# NodeMCU.net
KiCad netlist of a schematic drawn in Altium Designer
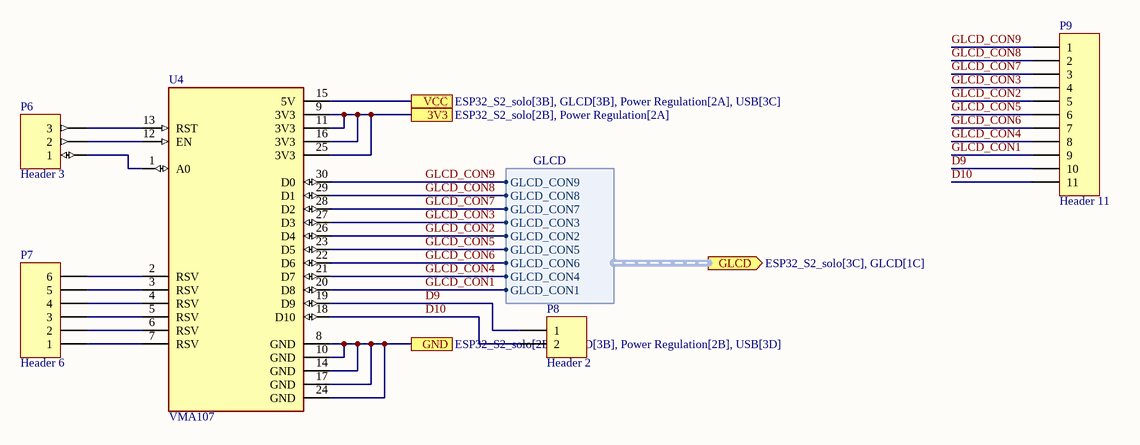
[diagram p0: NodeMCU.SchDoc]

(export (version "E")
  (design (tool "Eeschema 10.0.6"))
  (components
    (comp (ref "P6")
      (value "Header 3")
      (footprint "HDR1X3")
      (description "Header, 3-Pin")
      (fields (field (name "PUBLISHER") "Altium Limited"))
      (libsource (lib "Miscellaneous Connectors") (part "Header 3"))
    )
    (comp (ref "P7")
      (value "Header 6")
      (footprint "HDR1X6")
      (description "Header, 6-Pin")
      (fields (field (name "PUBLISHER") "Altium Limited"))
      (libsource (lib "Miscellaneous Connectors") (part "Header 6"))
    )
    (comp (ref "P8")
      (value "Header 2")
      (footprint "HDR1X2")
      (description "Header, 2-Pin")
      (fields (field (name "PUBLISHER") "Altium Limited"))
      (libsource (lib "Miscellaneous Connectors") (part "Header 2"))
    )
    (comp (ref "P9")
      (value "Header 11")
      (footprint "HDR1X11")
      (description "Header, 11-Pin")
      (fields (field (name "PUBLISHER") "Altium Limited"))
      (libsource (lib "Miscellaneous Connectors") (part "Header 11"))
    )
    (comp (ref "U4")
      (value "VMA107")
      (footprint "MODULE_VMA107")
      (description "NodeMCU V2 Lua Based ESP8266 Development Board")
      (fields (field (name "MF") "{'manufacturer': u'Velleman'}"))
      (libsource (lib "SnapEDA_Library") (part "VMA107"))
    )
  )
  (nets
    (net (code "2") (name "/3V3") (class "Default")
      (node (ref "U4") (pin "11") (pinfunction "3V3_11") (pintype "power_in"))
      (node (ref "U4") (pin "16") (pinfunction "3V3_16") (pintype "power_in"))
      (node (ref "U4") (pin "25") (pinfunction "3V3_25") (pintype "power_in"))
      (node (ref "U4") (pin "9") (pinfunction "3V3_9") (pintype "power_in"))
    )
    (net (code "3") (name "/D9") (class "Default")
      (node (ref "P8") (pin "1") (pinfunction "1_1") (pintype "passive"))
      (node (ref "P9") (pin "10") (pinfunction "10_10") (pintype "passive"))
      (node (ref "U4") (pin "19") (pinfunction "D9_19") (pintype "bidirectional"))
    )
    (net (code "4") (name "/D10") (class "Default")
      (node (ref "P8") (pin "2") (pinfunction "2_2") (pintype "passive"))
      (node (ref "P9") (pin "11") (pinfunction "11_11") (pintype "passive"))
      (node (ref "U4") (pin "18") (pinfunction "D10_18") (pintype "bidirectional"))
    )
    (net (code "5") (name "/GLCD_CON1") (class "Default")
      (node (ref "P9") (pin "9") (pinfunction "9_9") (pintype "passive"))
      (node (ref "U4") (pin "20") (pinfunction "D8_20") (pintype "bidirectional"))
    )
    (net (code "6") (name "/GLCD_CON2") (class "Default")
      (node (ref "P9") (pin "5") (pinfunction "5_5") (pintype "passive"))
      (node (ref "U4") (pin "26") (pinfunction "D4_26") (pintype "bidirectional"))
    )
    (net (code "7") (name "/GLCD_CON3") (class "Default")
      (node (ref "P9") (pin "4") (pinfunction "4_4") (pintype "passive"))
      (node (ref "U4") (pin "27") (pinfunction "D3_27") (pintype "bidirectional"))
    )
    (net (code "8") (name "/GLCD_CON4") (class "Default")
      (node (ref "P9") (pin "8") (pinfunction "8_8") (pintype "passive"))
      (node (ref "U4") (pin "21") (pinfunction "D7_21") (pintype "bidirectional"))
    )
    (net (code "9") (name "/GLCD_CON5") (class "Default")
      (node (ref "P9") (pin "6") (pinfunction "6_6") (pintype "passive"))
      (node (ref "U4") (pin "23") (pinfunction "D5_23") (pintype "bidirectional"))
    )
    (net (code "10") (name "/GLCD_CON6") (class "Default")
      (node (ref "P9") (pin "7") (pinfunction "7_7") (pintype "passive"))
      (node (ref "U4") (pin "22") (pinfunction "D6_22") (pintype "bidirectional"))
    )
    (net (code "11") (name "/GLCD_CON7") (class "Default")
      (node (ref "P9") (pin "3") (pinfunction "3_3") (pintype "passive"))
      (node (ref "U4") (pin "28") (pinfunction "D2_28") (pintype "bidirectional"))
    )
    (net (code "12") (name "/GLCD_CON8") (class "Default")
      (node (ref "P9") (pin "2") (pinfunction "2_2") (pintype "passive"))
      (node (ref "U4") (pin "29") (pinfunction "D1_29") (pintype "bidirectional"))
    )
    (net (code "13") (name "/GLCD_CON9") (class "Default")
      (node (ref "P9") (pin "1") (pinfunction "1_1") (pintype "passive"))
      (node (ref "U4") (pin "30") (pinfunction "D0_30") (pintype "bidirectional"))
    )
    (net (code "14") (name "/GND") (class "Default")
      (node (ref "U4") (pin "10") (pinfunction "GND_10") (pintype "power_in"))
      (node (ref "U4") (pin "14") (pinfunction "GND_14") (pintype "power_in"))
      (node (ref "U4") (pin "17") (pinfunction "GND_17") (pintype "power_in"))
      (node (ref "U4") (pin "24") (pinfunction "GND_24") (pintype "power_in"))
      (node (ref "U4") (pin "8") (pinfunction "GND_8") (pintype "power_in"))
    )
    (net (code "15") (name "/VCC") (class "Default")
      (node (ref "U4") (pin "15") (pinfunction "5V_15") (pintype "power_in"))
    )
    (net (code "17") (name "Net-(P7-Pad1)") (class "Default")
      (node (ref "P7") (pin "1") (pinfunction "1_1") (pintype "passive"))
      (node (ref "U4") (pin "7") (pinfunction "RSV_7") (pintype "passive"))
    )
    (net (code "18") (name "Net-(P7-Pad2)") (class "Default")
      (node (ref "P7") (pin "2") (pinfunction "2_2") (pintype "passive"))
      (node (ref "U4") (pin "6") (pinfunction "RSV_6") (pintype "passive"))
    )
    (net (code "19") (name "Net-(P7-Pad3)") (class "Default")
      (node (ref "P7") (pin "3") (pinfunction "3_3") (pintype "passive"))
      (node (ref "U4") (pin "5") (pinfunction "RSV_5") (pintype "passive"))
    )
    (net (code "20") (name "Net-(P7-Pad4)") (class "Default")
      (node (ref "P7") (pin "4") (pinfunction "4_4") (pintype "passive"))
      (node (ref "U4") (pin "4") (pinfunction "RSV_4") (pintype "passive"))
    )
    (net (code "21") (name "Net-(P7-Pad5)") (class "Default")
      (node (ref "P7") (pin "5") (pinfunction "5_5") (pintype "passive"))
      (node (ref "U4") (pin "3") (pinfunction "RSV_3") (pintype "passive"))
    )
    (net (code "22") (name "Net-(P7-Pad6)") (class "Default")
      (node (ref "P7") (pin "6") (pinfunction "6_6") (pintype "passive"))
      (node (ref "U4") (pin "2") (pinfunction "RSV_2") (pintype "passive"))
    )
    (net (code "23") (name "Net-(U4-A0)") (class "Default")
      (node (ref "P6") (pin "1") (pinfunction "1_1") (pintype "bidirectional"))
      (node (ref "U4") (pin "1") (pinfunction "A0_1") (pintype "bidirectional"))
    )
    (net (code "24") (name "Net-(U4-EN)") (class "Default")
      (node (ref "P6") (pin "2") (pinfunction "2_2") (pintype "output"))
      (node (ref "U4") (pin "12") (pinfunction "EN_12") (pintype "input"))
    )
    (net (code "25") (name "Net-(U4-RST)") (class "Default")
      (node (ref "P6") (pin "3") (pinfunction "3_3") (pintype "output"))
      (node (ref "U4") (pin "13") (pinfunction "RST_13") (pintype "input"))
    )
  )
)
